# PowerSupply.net
KiCad netlist of a schematic drawn in Altium Designer
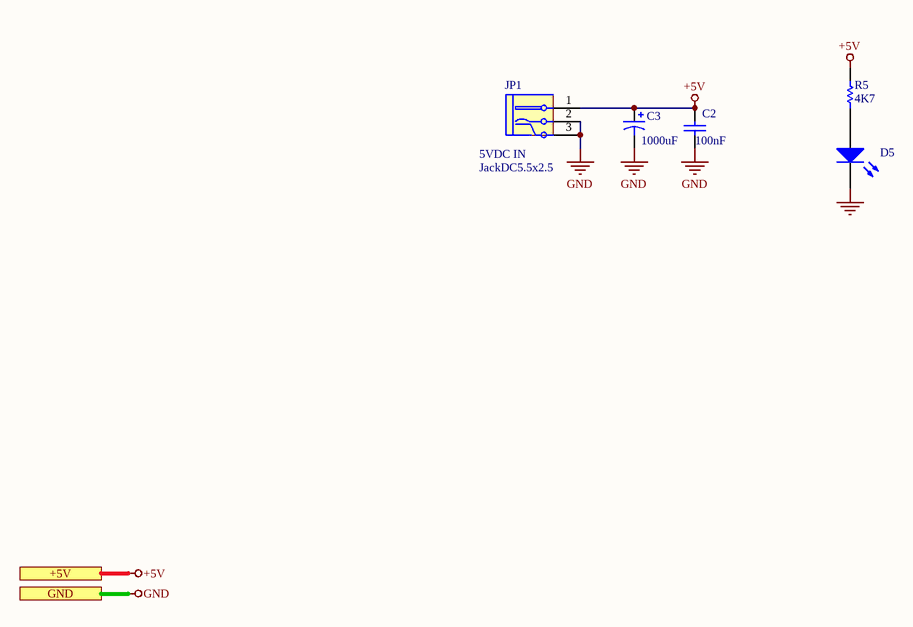
[diagram p0: PowerSupply.SchDoc]

(export (version "E")
  (design (tool "Eeschema 10.0.6"))
  (components
    (comp (ref "C2")
      (value "100nF")
      (footprint "C-0805")
      (description "Capacitor")
      (fields (field (name "Comment") "104") (field (name "PUBLISHER") "Altium Limited"))
      (libsource (lib "Miscellaneous Devices") (part "Cap"))
    )
    (comp (ref "C3")
      (value "1000uF")
      (footprint "RB7.6-15")
      (description "Polarized Capacitor (Radial)")
      (fields (field (name "Comment") "1000uF/16V") (field (name "PUBLISHER") "Altium Limited"))
      (libsource (lib "Miscellaneous Devices") (part "Cap Pol1"))
    )
    (comp (ref "D5")
      (value "SMD0805-RED")
      (footprint "LED-0805")
      (description "Typical INFRARED GaAs LED")
      (libsource (lib "Miscellaneous Devices") (part "LED0"))
    )
    (comp (ref "JP1")
      (value "JackDC5.5x2.5")
      (description "Jack DC5.5x2.5MM DC5525")
      (fields (field (name "ALTIUM_VALUE") "5VDC IN"))
      (libsource (lib "Dlib") (part "JACK DC5.5x2.5"))
    )
    (comp (ref "R5")
      (value "4K7")
      (footprint "R-0805")
      (description "Resistor")
      (fields (field (name "PUBLISHER") "Altium Limited"))
      (libsource (lib "Miscellaneous Devices") (part "Res1"))
    )
  )
  (nets
    (net (code "1") (name "+5V") (class "Default")
      (node (ref "C2") (pin "1") (pinfunction "1_1") (pintype "passive"))
      (node (ref "C3") (pin "1") (pinfunction "1_1") (pintype "passive"))
      (node (ref "JP1") (pin "1") (pinfunction "T_1") (pintype "passive"))
      (node (ref "R5") (pin "2") (pinfunction "2_2") (pintype "passive"))
    )
    (net (code "2") (name "GND") (class "Default")
      (node (ref "C2") (pin "2") (pinfunction "2_2") (pintype "passive"))
      (node (ref "C3") (pin "2") (pinfunction "2_2") (pintype "passive"))
      (node (ref "D5") (pin "2") (pinfunction "K_2") (pintype "passive"))
      (node (ref "JP1") (pin "2") (pinfunction "TN_2") (pintype "passive"))
      (node (ref "JP1") (pin "3") (pinfunction "S_3") (pintype "power_in"))
    )
    (net (code "3") (name "Net-(D5-A)") (class "Default")
      (node (ref "D5") (pin "1") (pinfunction "A_1") (pintype "passive"))
      (node (ref "R5") (pin "1") (pinfunction "1_1") (pintype "passive"))
    )
  )
)
